# blink_routed.net
KiCad netlist of a schematic drawn in Altium Designer
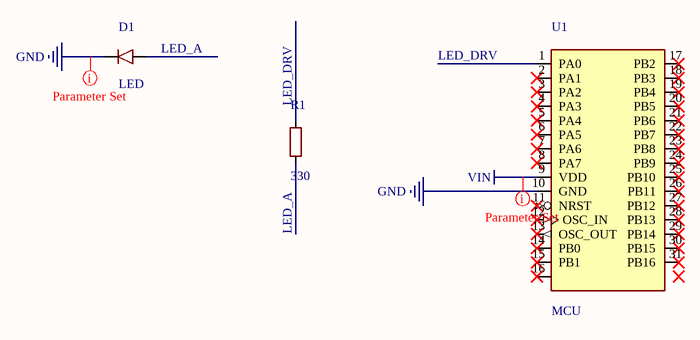
[diagram p0: blink_routed.SchDoc]

(export (version "E")
  (design (tool "Eeschema 10.0.6"))
  (components
    (comp (ref "D1")
      (value "LED")
      (footprint "blink_routed:Mini_LED_THT_3mm")
      (libsource (lib "blink_routed") (part "Mini_LED"))
    )
    (comp (ref "R1")
      (value "330")
      (footprint "blink_routed:Mini_R_0603")
      (libsource (lib "blink_routed") (part "Mini_R"))
    )
    (comp (ref "U1")
      (value "MCU")
      (footprint "blink_routed:Mini_QFP-32_7x7mm_P0.8mm")
      (libsource (lib "blink_routed") (part "Mini_QFP32_IC"))
    )
  )
  (nets
    (net (code "1") (name "/LED_A") (class "Default")
      (node (ref "D1") (pin "2") (pinfunction "A_2") (pintype "passive"))
      (node (ref "R1") (pin "2") (pintype "passive"))
    )
    (net (code "2") (name "/LED_DRV") (class "Default")
      (node (ref "R1") (pin "1") (pintype "passive"))
      (node (ref "U1") (pin "1") (pinfunction "PA0_1") (pintype "bidirectional"))
    )
    (net (code "3") (name "GND") (class "Default")
      (node (ref "D1") (pin "1") (pinfunction "K_1") (pintype "passive"))
      (node (ref "U1") (pin "10") (pinfunction "GND_10") (pintype "power_in"))
    )
    (net (code "4") (name "VIN") (class "Default")
      (node (ref "U1") (pin "9") (pinfunction "VDD_9") (pintype "power_in"))
    )
    (net (code "5") (name "unconnected-(U1-EP-Pad32)") (class "Default")
      (node (ref "U1") (pin "32") (pinfunction "EP_32") (pintype "passive+no_connect"))
    )
    (net (code "6") (name "unconnected-(U1-NRST-Pad11)") (class "Default")
      (node (ref "U1") (pin "11") (pinfunction "NRST_11") (pintype "input+no_connect"))
    )
    (net (code "7") (name "unconnected-(U1-OSC_IN-Pad12)") (class "Default")
      (node (ref "U1") (pin "12") (pinfunction "OSC_IN_12") (pintype "input+no_connect"))
    )
    (net (code "8") (name "unconnected-(U1-OSC_OUT-Pad13)") (class "Default")
      (node (ref "U1") (pin "13") (pinfunction "OSC_OUT_13") (pintype "output+no_connect"))
    )
    (net (code "9") (name "unconnected-(U1-PA1-Pad2)") (class "Default")
      (node (ref "U1") (pin "2") (pinfunction "PA1_2") (pintype "bidirectional+no_connect"))
    )
    (net (code "10") (name "unconnected-(U1-PA2-Pad3)") (class "Default")
      (node (ref "U1") (pin "3") (pinfunction "PA2_3") (pintype "bidirectional+no_connect"))
    )
    (net (code "11") (name "unconnected-(U1-PA3-Pad4)") (class "Default")
      (node (ref "U1") (pin "4") (pinfunction "PA3_4") (pintype "bidirectional+no_connect"))
    )
    (net (code "12") (name "unconnected-(U1-PA4-Pad5)") (class "Default")
      (node (ref "U1") (pin "5") (pinfunction "PA4_5") (pintype "bidirectional+no_connect"))
    )
    (net (code "13") (name "unconnected-(U1-PA5-Pad6)") (class "Default")
      (node (ref "U1") (pin "6") (pinfunction "PA5_6") (pintype "bidirectional+no_connect"))
    )
    (net (code "14") (name "unconnected-(U1-PA6-Pad7)") (class "Default")
      (node (ref "U1") (pin "7") (pinfunction "PA6_7") (pintype "bidirectional+no_connect"))
    )
    (net (code "15") (name "unconnected-(U1-PA7-Pad8)") (class "Default")
      (node (ref "U1") (pin "8") (pinfunction "PA7_8") (pintype "bidirectional+no_connect"))
    )
    (net (code "16") (name "unconnected-(U1-PB0-Pad14)") (class "Default")
      (node (ref "U1") (pin "14") (pinfunction "PB0_14") (pintype "bidirectional+no_connect"))
    )
    (net (code "17") (name "unconnected-(U1-PB1-Pad15)") (class "Default")
      (node (ref "U1") (pin "15") (pinfunction "PB1_15") (pintype "tri_state+no_connect"))
    )
    (net (code "18") (name "unconnected-(U1-PB2-Pad17)") (class "Default")
      (node (ref "U1") (pin "17") (pinfunction "PB2_17") (pintype "bidirectional+no_connect"))
    )
    (net (code "19") (name "unconnected-(U1-PB3-Pad18)") (class "Default")
      (node (ref "U1") (pin "18") (pinfunction "PB3_18") (pintype "bidirectional+no_connect"))
    )
    (net (code "20") (name "unconnected-(U1-PB4-Pad19)") (class "Default")
      (node (ref "U1") (pin "19") (pinfunction "PB4_19") (pintype "bidirectional+no_connect"))
    )
    (net (code "21") (name "unconnected-(U1-PB5-Pad20)") (class "Default")
      (node (ref "U1") (pin "20") (pinfunction "PB5_20") (pintype "bidirectional+no_connect"))
    )
    (net (code "22") (name "unconnected-(U1-PB6-Pad21)") (class "Default")
      (node (ref "U1") (pin "21") (pinfunction "PB6_21") (pintype "bidirectional+no_connect"))
    )
    (net (code "23") (name "unconnected-(U1-PB7-Pad22)") (class "Default")
      (node (ref "U1") (pin "22") (pinfunction "PB7_22") (pintype "bidirectional+no_connect"))
    )
    (net (code "24") (name "unconnected-(U1-PB8-Pad23)") (class "Default")
      (node (ref "U1") (pin "23") (pinfunction "PB8_23") (pintype "bidirectional+no_connect"))
    )
    (net (code "25") (name "unconnected-(U1-PB9-Pad24)") (class "Default")
      (node (ref "U1") (pin "24") (pinfunction "PB9_24") (pintype "bidirectional+no_connect"))
    )
    (net (code "26") (name "unconnected-(U1-PB10-Pad25)") (class "Default")
      (node (ref "U1") (pin "25") (pinfunction "PB10_25") (pintype "bidirectional+no_connect"))
    )
    (net (code "27") (name "unconnected-(U1-PB11-Pad26)") (class "Default")
      (node (ref "U1") (pin "26") (pinfunction "PB11_26") (pintype "bidirectional+no_connect"))
    )
    (net (code "28") (name "unconnected-(U1-PB12-Pad27)") (class "Default")
      (node (ref "U1") (pin "27") (pinfunction "PB12_27") (pintype "bidirectional+no_connect"))
    )
    (net (code "29") (name "unconnected-(U1-PB13-Pad28)") (class "Default")
      (node (ref "U1") (pin "28") (pinfunction "PB13_28") (pintype "bidirectional+no_connect"))
    )
    (net (code "30") (name "unconnected-(U1-PB14-Pad29)") (class "Default")
      (node (ref "U1") (pin "29") (pinfunction "PB14_29") (pintype "bidirectional+no_connect"))
    )
    (net (code "31") (name "unconnected-(U1-PB15-Pad30)") (class "Default")
      (node (ref "U1") (pin "30") (pinfunction "PB15_30") (pintype "bidirectional+no_connect"))
    )
    (net (code "32") (name "unconnected-(U1-PB16-Pad31)") (class "Default")
      (node (ref "U1") (pin "31") (pinfunction "PB16_31") (pintype "bidirectional+no_connect"))
    )
    (net (code "33") (name "unconnected-(U1-Pad16)") (class "Default")
      (node (ref "U1") (pin "16") (pintype "passive+no_connect"))
    )
  )
)
